# USB_to_UART.net
KiCad netlist of a schematic drawn in Altium Designer
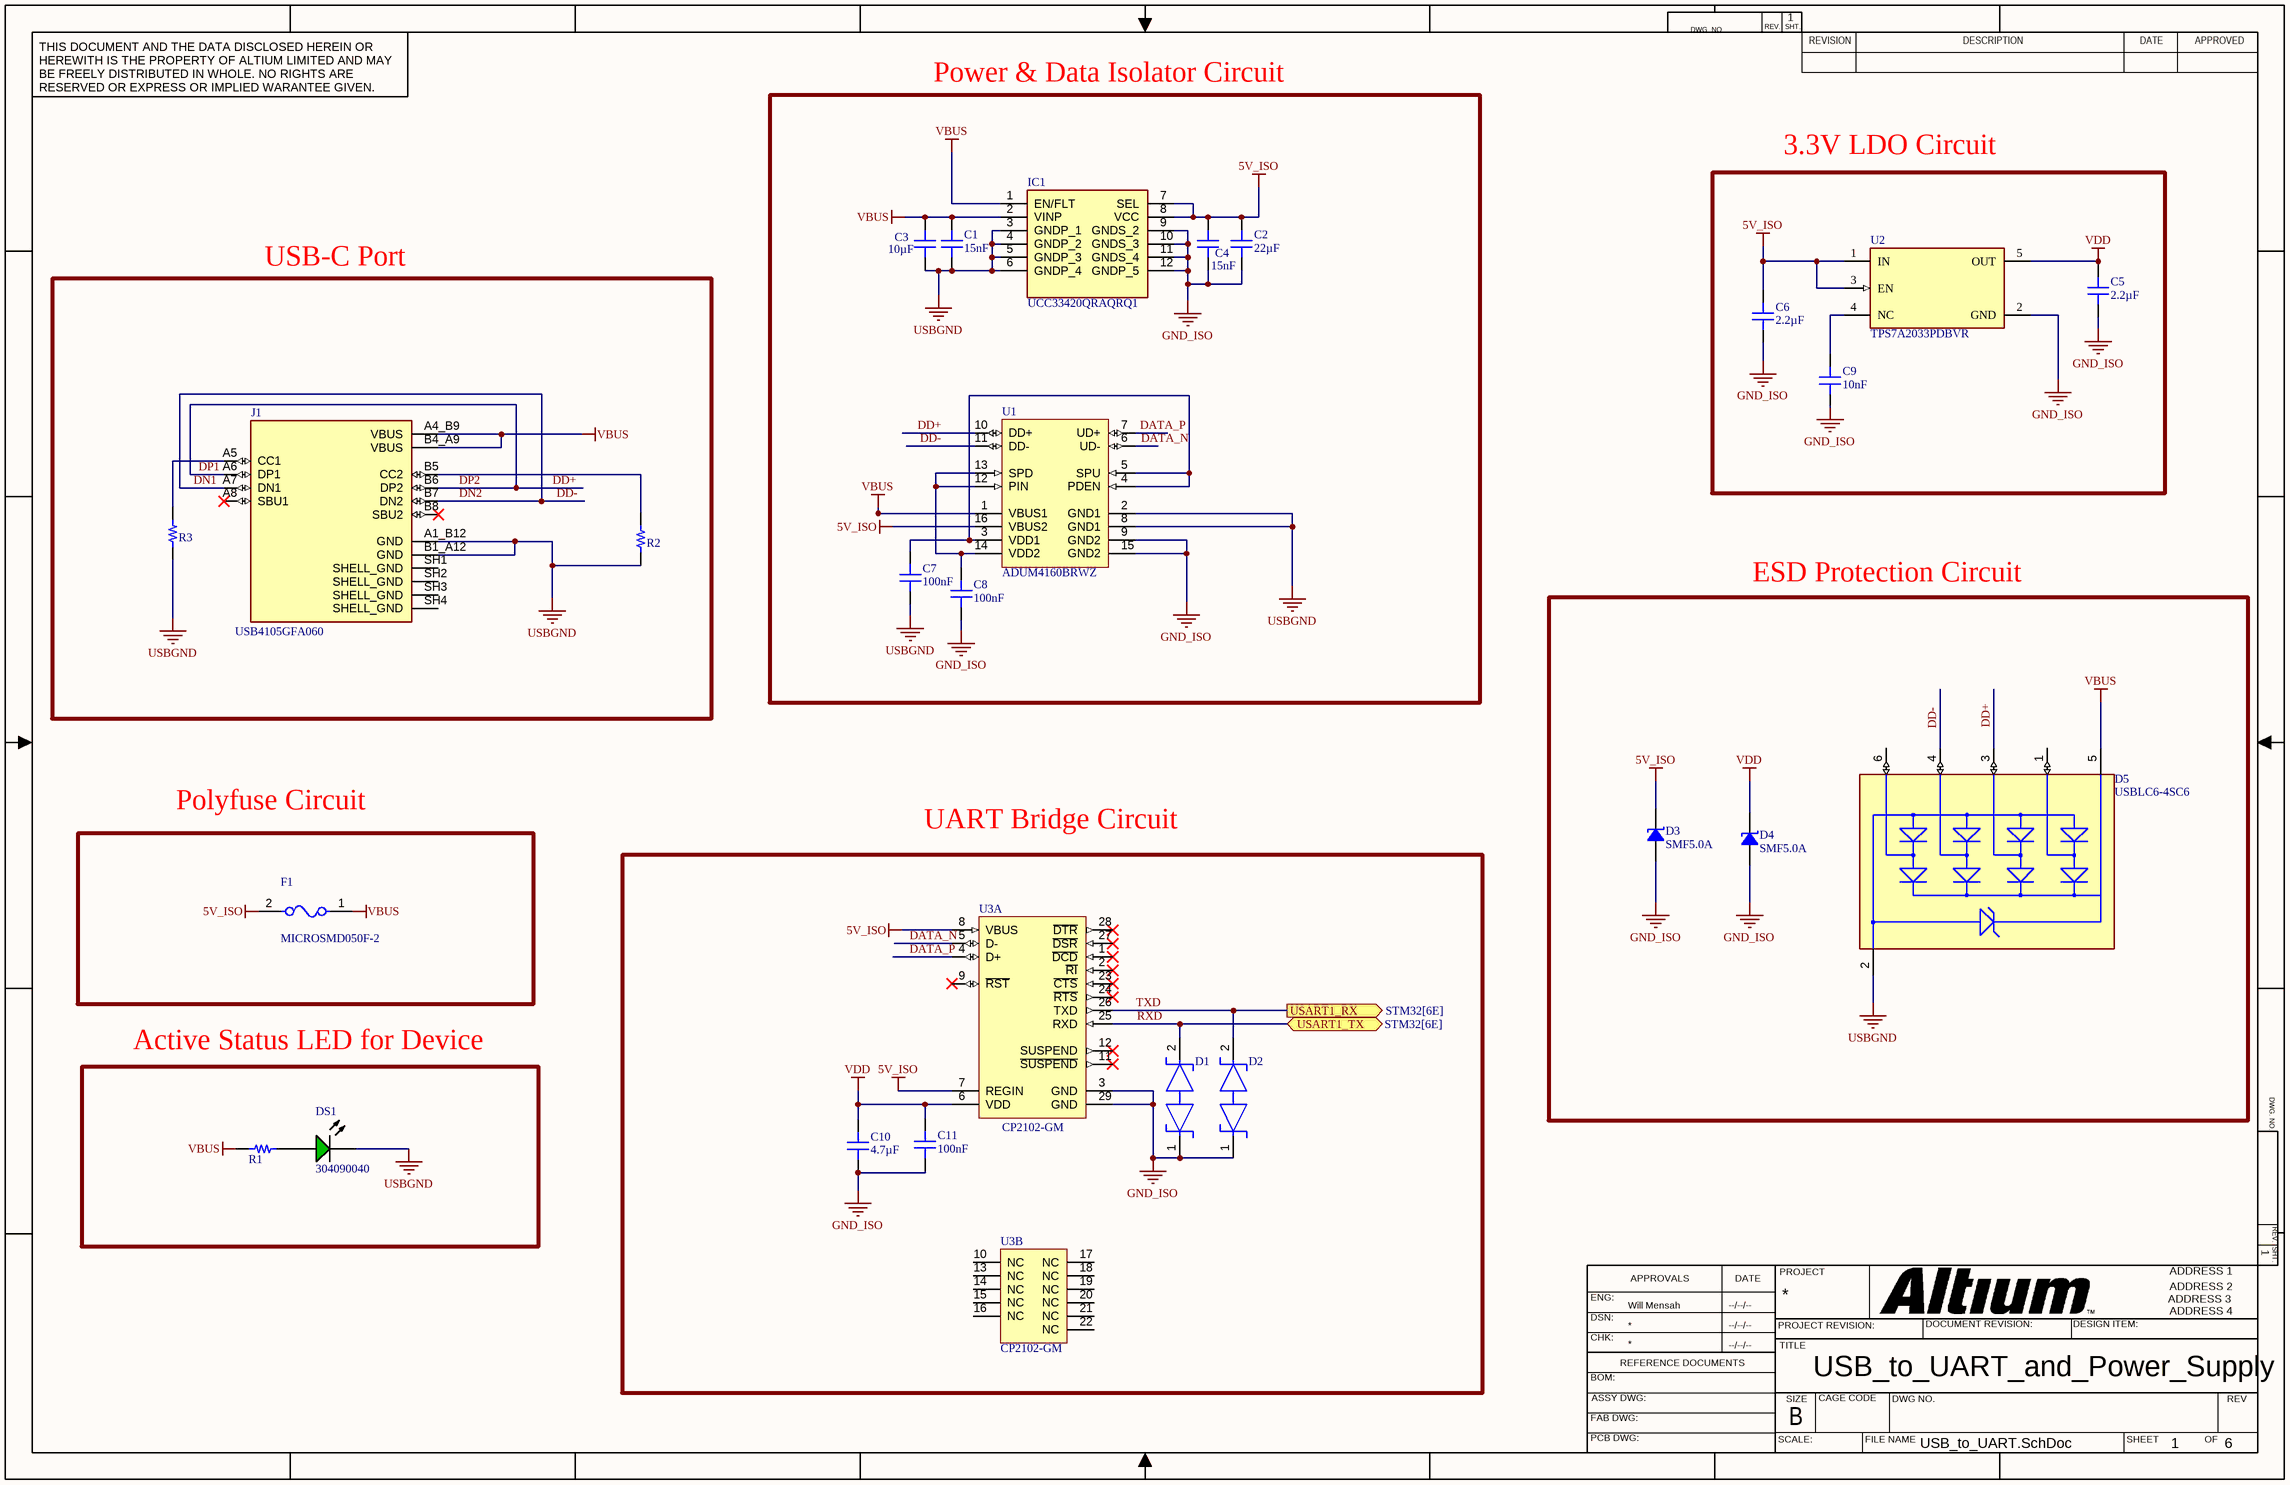
[diagram p0: USB_to_UART.SchDoc]

(export (version "E")
  (design (tool "Eeschema 10.0.6"))
  (components
    (comp (ref "C1")
      (value "15nF")
      (footprint "CAP 1206_3216 - 0.8MM")
      (description "CAP CER 15000PF 630V X7R 1206")
      (fields (field (name "PART NUMBER") "885342208013"))
      (libsource (lib "University of Massachusetts Lowell") (part "CAPACITOR"))
    )
    (comp (ref "C2")
      (value "22µF")
      (footprint "MURATA - GRM32E")
      (description "CAP CER 22UF 25V X7R 1210")
      (fields (field (name "PART NUMBER") "GRM32ER71E226ME15L"))
      (libsource (lib "University of Massachusetts Lowell") (part "CAPACITOR"))
    )
    (comp (ref "C3")
      (value "10µF")
      (footprint "MURATA - GRM32E")
      (description "CAP CER 10UF 50V X7R 1210")
      (fields (field (name "PART NUMBER") "GRM32ER71H106MA12L"))
      (libsource (lib "University of Massachusetts Lowell") (part "CAPACITOR"))
    )
    (comp (ref "C4")
      (value "15nF")
      (footprint "CAP 1206_3216 - 0.8MM")
      (description "CAP CER 15000PF 630V X7R 1206")
      (fields (field (name "PART NUMBER") "885342208013"))
      (libsource (lib "University of Massachusetts Lowell") (part "CAPACITOR"))
    )
    (comp (ref "C5")
      (value "2.2µF")
      (footprint "MURATA CAP GCM31M 1206_3216")
      (description "CAP CER 2.2UF 100V X8L 1206")
      (fields (field (name "PART NUMBER") "GCM31CL8EL225KE07L"))
      (libsource (lib "University of Massachusetts Lowell") (part "CAPACITOR"))
    )
    (comp (ref "C6")
      (value "2.2µF")
      (footprint "MURATA CAP GCM31M 1206_3216")
      (description "CAP CER 2.2UF 100V X8L 1206")
      (fields (field (name "PART NUMBER") "GCM31CL8EL225KE07L"))
      (libsource (lib "University of Massachusetts Lowell") (part "CAPACITOR"))
    )
    (comp (ref "C7")
      (value "100nF")
      (footprint "MURATA CAP GCM31M 1206_3216")
      (description "CAP CER 0.1UF 50V C0G/NP0 1206")
      (fields (field (name "PART NUMBER") "GCM31C5C1H104FA16L"))
      (libsource (lib "University of Massachusetts Lowell") (part "CAPACITOR"))
    )
    (comp (ref "C8")
      (value "100nF")
      (footprint "MURATA CAP GCM31M 1206_3216")
      (description "CAP CER 0.1UF 50V C0G/NP0 1206")
      (fields (field (name "PART NUMBER") "GCM31C5C1H104FA16L"))
      (libsource (lib "University of Massachusetts Lowell") (part "CAPACITOR"))
    )
    (comp (ref "C9")
      (value "10nF")
      (footprint "MURATA CAP GRM31B 1206_3216")
      (description "CAP CER 10000PF 250V U2J 1206")
      (fields (field (name "PART NUMBER") "GRM31B7U2E103JW31L"))
      (libsource (lib "University of Massachusetts Lowell") (part "CAPACITOR"))
    )
    (comp (ref "C10")
      (value "4.7µF")
      (footprint "MURATA GRM21B 0805_2012")
      (description "CAP CER 4.7UF 10V X7R 0805")
      (fields (field (name "PART NUMBER") "GRM21BR71A475KE51L"))
      (libsource (lib "University of Massachusetts Lowell") (part "CAPACITOR"))
    )
    (comp (ref "C11")
      (value "100nF")
      (footprint "MURATA CAP GCM31M 1206_3216")
      (description "CAP CER 0.1UF 50V C0G/NP0 1206")
      (fields (field (name "PART NUMBER") "GCM31C5C1H104FA16L"))
      (libsource (lib "University of Massachusetts Lowell") (part "CAPACITOR"))
    )
    (comp (ref "D1")
      (value "TPD1E10B06DPYR")
      (footprint "FP-DPY0002A-MFG")
      (description "TVS DIODE 5.5V 14V 2X1SON")
      (fields (field (name "MANUFACTURER") "Texas Instruments"))
      (libsource (lib "Altium Content Vault") (part "208e19b57522434895fa003e5d5b197"))
    )
    (comp (ref "D2")
      (value "TPD1E10B06DPYR")
      (footprint "FP-DPY0002A-MFG")
      (description "TVS DIODE 5.5V 14V 2X1SON")
      (fields (field (name "MANUFACTURER") "Texas Instruments"))
      (libsource (lib "Altium Content Vault") (part "208e19b57522434895fa003e5d5b197"))
    )
    (comp (ref "D3")
      (value "SMF5.0A")
      (footprint "SOD123F")
      (description "TVS SOD123FL 5V 200W UNIDIR")
      (libsource (lib "University of Massachusetts Lowell") (part "DIODE TVS UNI"))
    )
    (comp (ref "D4")
      (value "SMF5.0A")
      (footprint "SOD123F")
      (description "TVS SOD123FL 5V 200W UNIDIR")
      (libsource (lib "University of Massachusetts Lowell") (part "DIODE TVS UNI"))
    )
    (comp (ref "D5")
      (value "USBLC6-4SC6")
      (footprint "FP-SOT23-6L-MFG")
      (description "TVS DIODE 5.25V 17V SOT23-6")
      (fields
        (field (name "MANUFACTURER") "STMicroelectronics")
        (field (name "OCTOPART") "https://octopart.com/usblc6-4sc6-stmicroelectronics-347147")
      )
      (libsource (lib "Altium Content Vault") (part "3e70b616ccdc4c88b528e1820c4a7da"))
    )
    (comp (ref "DS1")
      (value "304090040")
      (footprint "LED-2P-2.28-3MM")
      (description "Green LED, 80 mW, 20 mA, -25 to 85 degC, 2-Pin THD")
      (fields (field (name "MANUFACTURER") "Shenzhen CGX"))
      (libsource (lib "University of Massachusetts Lowell") (part "LED-GREEN-AK-2"))
    )
    (comp (ref "F1")
      (value "MICROSMD050F-2")
      (footprint "FP-microSMD-MFG")
      (description "PTC RESET FUSE 13.2V 500MA 1210")
      (fields
        (field (name "MANUFACTURER") "Littelfuse")
        (field (name "OCTOPART") "https://octopart.com/microsmd050f-2-littelfuse-74214982")
      )
      (libsource (lib "Altium Content Vault") (part "5bcf9b9f640e542cf0359d10258e979"))
    )
    (comp (ref "IC1")
      (value "UCC33420QRAQRQ1")
      (footprint "SamacSys:UCC33020QRAQRQ1")
      (description "Integrated Circuit")
      (fields (field (name "MOUSER PART NUMBER") "595-UCC33420QRAQRQ1"))
      (libsource (lib "*") (part "UCC33420QRAQRQ1"))
    )
    (comp (ref "J1")
      (value "USB4105GFA060")
      (footprint "GCT_USB4105GFA060")
      (fields (field (name "MF") "Global Connector Technology"))
      (libsource (lib "University of Massachusetts Lowell") (part "USB4105GFA060"))
    )
    (comp (ref "R1")
      (value "RC1206FR-101KL")
      (footprint "YAGEO RES 1206_3216")
      (description "RES 1K OHM 1% 1/4W 1206")
      (libsource (lib "University of Massachusetts Lowell") (part "RESISTOR"))
    )
    (comp (ref "R2")
      (value "RP1206BRD075K1L")
      (footprint "YAGEO RES 1206_3216")
      (description "RES 5.1K OHM 0.1% 1/4W 1206")
      (libsource (lib "University of Massachusetts Lowell") (part "RESISTOR"))
    )
    (comp (ref "R3")
      (value "RP1206BRD075K1L")
      (footprint "YAGEO RES 1206_3216")
      (description "RES 5.1K OHM 0.1% 1/4W 1206")
      (libsource (lib "University of Massachusetts Lowell") (part "RESISTOR"))
    )
    (comp (ref "U1")
      (value "ADUM4160BRWZ")
      (footprint "RW-16_L")
      (fields (field (name "MANUFACTURER") "Analog Devices"))
      (libsource (lib "Altium Content Vault") (part "ADI-ADUM4160-16"))
    )
    (comp (ref "U2")
      (value "TPS7A2033PDBVR")
      (footprint "FP-DBV0005A-MFG")
      (description "IC REG LINEAR 3.3V 300MA SOT23-5")
      (libsource (lib "Altium Content Vault") (part "76aa7ad0ceb1012e0d85aeafc53095f"))
    )
    (comp (ref "U3")
      (value "CP2102-GM")
      (footprint "SLAB-QFN-28-3125x3125TP_N")
      (description "Single-Chip USB to UART Bridge, 1024 Bytes EEPROM, -40 to 85 degC, 28-pin QFN, Tube")
      (fields (field (name "MANUFACTURER") "Silicon Labs"))
      (libsource (lib "Altium Content Vault") (part "SLAB-CP210X-QFN-28-29"))
    )
  )
  (nets
    (net (code "1") (name "/DATA_N") (class "Default")
      (node (ref "U1") (pin "6") (pinfunction "UD-_6") (pintype "bidirectional"))
      (node (ref "U3") (pin "5") (pinfunction "D-_5") (pintype "bidirectional"))
    )
    (net (code "2") (name "/DATA_P") (class "Default")
      (node (ref "U1") (pin "7") (pinfunction "UD+_7") (pintype "bidirectional"))
      (node (ref "U3") (pin "4") (pinfunction "D+_4") (pintype "bidirectional"))
    )
    (net (code "3") (name "/DD+") (class "Default")
      (node (ref "D5") (pin "3") (pinfunction "I/O2_3") (pintype "bidirectional"))
      (node (ref "J1") (pin "A6") (pinfunction "DP1_A6") (pintype "bidirectional"))
      (node (ref "J1") (pin "B6") (pinfunction "DP2_B6") (pintype "bidirectional"))
      (node (ref "U1") (pin "10") (pinfunction "DD+_10") (pintype "bidirectional"))
    )
    (net (code "4") (name "/DD-") (class "Default")
      (node (ref "D5") (pin "4") (pinfunction "I/O3_4") (pintype "bidirectional"))
      (node (ref "J1") (pin "A7") (pinfunction "DN1_A7") (pintype "bidirectional"))
      (node (ref "J1") (pin "B7") (pinfunction "DN2_B7") (pintype "bidirectional"))
      (node (ref "U1") (pin "11") (pinfunction "DD-_11") (pintype "bidirectional"))
    )
    (net (code "5") (name "/RXD") (class "Default")
      (node (ref "D1") (pin "2") (pinfunction "2_2") (pintype "passive"))
      (node (ref "U3") (pin "25") (pinfunction "RXD_25") (pintype "input"))
    )
    (net (code "6") (name "/TXD") (class "Default")
      (node (ref "D2") (pin "2") (pinfunction "2_2") (pintype "passive"))
      (node (ref "U3") (pin "26") (pinfunction "TXD_26") (pintype "output"))
    )
    (net (code "7") (name "5V_ISO") (class "Default")
      (node (ref "C2") (pin "2") (pinfunction "2_2") (pintype "passive"))
      (node (ref "C4") (pin "2") (pinfunction "2_2") (pintype "passive"))
      (node (ref "C6") (pin "2") (pinfunction "2_2") (pintype "passive"))
      (node (ref "D3") (pin "2") (pinfunction "2_2") (pintype "passive"))
      (node (ref "F1") (pin "2") (pinfunction "2_2") (pintype "passive"))
      (node (ref "IC1") (pin "7") (pinfunction "SEL_7") (pintype "passive"))
      (node (ref "IC1") (pin "8") (pinfunction "VCC_8") (pintype "passive"))
      (node (ref "U1") (pin "16") (pinfunction "VBUS2_16") (pintype "power_in"))
      (node (ref "U2") (pin "1") (pinfunction "IN_1") (pintype "power_in"))
      (node (ref "U2") (pin "3") (pinfunction "EN_3") (pintype "input"))
      (node (ref "U3") (pin "7") (pinfunction "REGIN_7") (pintype "power_in"))
      (node (ref "U3") (pin "8") (pinfunction "VBUS_8") (pintype "input"))
    )
    (net (code "8") (name "GND_ISO") (class "Default")
      (node (ref "C10") (pin "1") (pinfunction "1_1") (pintype "passive"))
      (node (ref "C11") (pin "1") (pinfunction "1_1") (pintype "passive"))
      (node (ref "C2") (pin "1") (pinfunction "1_1") (pintype "passive"))
      (node (ref "C4") (pin "1") (pinfunction "1_1") (pintype "passive"))
      (node (ref "C5") (pin "1") (pinfunction "1_1") (pintype "passive"))
      (node (ref "C6") (pin "1") (pinfunction "1_1") (pintype "passive"))
      (node (ref "C8") (pin "1") (pinfunction "1_1") (pintype "passive"))
      (node (ref "C9") (pin "1") (pinfunction "1_1") (pintype "passive"))
      (node (ref "D1") (pin "1") (pinfunction "1_1") (pintype "passive"))
      (node (ref "D2") (pin "1") (pinfunction "1_1") (pintype "passive"))
      (node (ref "D3") (pin "1") (pinfunction "1_1") (pintype "passive"))
      (node (ref "D4") (pin "1") (pinfunction "1_1") (pintype "passive"))
      (node (ref "IC1") (pin "10") (pinfunction "GNDS_3_10") (pintype "passive"))
      (node (ref "IC1") (pin "11") (pinfunction "GNDS_4_11") (pintype "passive"))
      (node (ref "IC1") (pin "12") (pinfunction "GNDP_5_12") (pintype "passive"))
      (node (ref "IC1") (pin "9") (pinfunction "GNDS_2_9") (pintype "passive"))
      (node (ref "U1") (pin "15") (pinfunction "GND2_15") (pintype "power_in"))
      (node (ref "U1") (pin "9") (pinfunction "GND2_9") (pintype "power_in"))
      (node (ref "U2") (pin "2") (pinfunction "GND_2") (pintype "power_in"))
      (node (ref "U3") (pin "29") (pinfunction "GND_29") (pintype "power_in"))
      (node (ref "U3") (pin "3") (pinfunction "GND_3") (pintype "power_in"))
    )
    (net (code "9") (name "Net-(DS1-A)") (class "Default")
      (node (ref "DS1") (pin "1") (pinfunction "A_1") (pintype "passive"))
      (node (ref "R1") (pin "1") (pinfunction "1_1") (pintype "passive"))
    )
    (net (code "10") (name "Net-(J1-CC1)") (class "Default")
      (node (ref "J1") (pin "A5") (pinfunction "CC1_A5") (pintype "bidirectional"))
      (node (ref "R3") (pin "1") (pinfunction "1_1") (pintype "passive"))
    )
    (net (code "11") (name "Net-(J1-CC2)") (class "Default")
      (node (ref "J1") (pin "B5") (pinfunction "CC2_B5") (pintype "bidirectional"))
      (node (ref "R2") (pin "2") (pinfunction "2_2") (pintype "passive"))
    )
    (net (code "12") (name "Net-(U1-PDEN)") (class "Default")
      (node (ref "C7") (pin "2") (pinfunction "2_2") (pintype "passive"))
      (node (ref "U1") (pin "3") (pinfunction "VDD1_3") (pintype "power_in"))
      (node (ref "U1") (pin "4") (pinfunction "PDEN_4") (pintype "input"))
      (node (ref "U1") (pin "5") (pinfunction "SPU_5") (pintype "input"))
    )
    (net (code "13") (name "Net-(U1-PIN)") (class "Default")
      (node (ref "C8") (pin "2") (pinfunction "2_2") (pintype "passive"))
      (node (ref "U1") (pin "12") (pinfunction "PIN_12") (pintype "input"))
      (node (ref "U1") (pin "13") (pinfunction "SPD_13") (pintype "input"))
      (node (ref "U1") (pin "14") (pinfunction "VDD2_14") (pintype "power_in"))
    )
    (net (code "14") (name "Net-(U2-NC)") (class "Default")
      (node (ref "C9") (pin "2") (pinfunction "2_2") (pintype "passive"))
      (node (ref "U2") (pin "4") (pinfunction "NC_4") (pintype "passive"))
    )
    (net (code "15") (name "USBGND") (class "Default")
      (node (ref "C1") (pin "1") (pinfunction "1_1") (pintype "passive"))
      (node (ref "C3") (pin "1") (pinfunction "1_1") (pintype "passive"))
      (node (ref "C7") (pin "1") (pinfunction "1_1") (pintype "passive"))
      (node (ref "D5") (pin "2") (pinfunction "GND_2") (pintype "power_in"))
      (node (ref "DS1") (pin "2") (pinfunction "K_2") (pintype "passive"))
      (node (ref "IC1") (pin "3") (pinfunction "GNDP_1_3") (pintype "passive"))
      (node (ref "IC1") (pin "4") (pinfunction "GNDP_2_4") (pintype "passive"))
      (node (ref "IC1") (pin "5") (pinfunction "GNDP_3_5") (pintype "passive"))
      (node (ref "IC1") (pin "6") (pinfunction "GNDP_4_6") (pintype "passive"))
      (node (ref "J1") (pin "A1_B12") (pinfunction "GND_A1_B12") (pintype "power_in"))
      (node (ref "J1") (pin "B1_A12") (pinfunction "GND_B1_A12") (pintype "power_in"))
      (node (ref "R2") (pin "1") (pinfunction "1_1") (pintype "passive"))
      (node (ref "R3") (pin "2") (pinfunction "2_2") (pintype "passive"))
      (node (ref "U1") (pin "2") (pinfunction "GND1_2") (pintype "power_in"))
      (node (ref "U1") (pin "8") (pinfunction "GND1_8") (pintype "power_in"))
    )
    (net (code "16") (name "VBUS") (class "Default")
      (node (ref "C1") (pin "2") (pinfunction "2_2") (pintype "passive"))
      (node (ref "C3") (pin "2") (pinfunction "2_2") (pintype "passive"))
      (node (ref "D5") (pin "5") (pinfunction "VBUS_5") (pintype "power_in"))
      (node (ref "F1") (pin "1") (pinfunction "1_1") (pintype "passive"))
      (node (ref "IC1") (pin "1") (pinfunction "EN/FLT_1") (pintype "passive"))
      (node (ref "IC1") (pin "2") (pinfunction "VINP_2") (pintype "passive"))
      (node (ref "J1") (pin "A4_B9") (pinfunction "VBUS_A4_B9") (pintype "power_in"))
      (node (ref "J1") (pin "B4_A9") (pinfunction "VBUS_B4_A9") (pintype "power_in"))
      (node (ref "R1") (pin "2") (pinfunction "2_2") (pintype "passive"))
      (node (ref "U1") (pin "1") (pinfunction "VBUS1_1") (pintype "power_in"))
    )
    (net (code "17") (name "VDD") (class "Default")
      (node (ref "C10") (pin "2") (pinfunction "2_2") (pintype "passive"))
      (node (ref "C11") (pin "2") (pinfunction "2_2") (pintype "passive"))
      (node (ref "C5") (pin "2") (pinfunction "2_2") (pintype "passive"))
      (node (ref "D4") (pin "2") (pinfunction "2_2") (pintype "passive"))
      (node (ref "U2") (pin "5") (pinfunction "OUT_5") (pintype "passive"))
      (node (ref "U3") (pin "6") (pinfunction "VDD_6") (pintype "power_in"))
    )
    (net (code "18") (name "unconnected-(D5-I{slash}O1-Pad1)") (class "Default")
      (node (ref "D5") (pin "1") (pinfunction "I/O1_1") (pintype "bidirectional"))
    )
    (net (code "19") (name "unconnected-(D5-I{slash}O4-Pad6)") (class "Default")
      (node (ref "D5") (pin "6") (pinfunction "I/O4_6") (pintype "bidirectional"))
    )
    (net (code "20") (name "unconnected-(J1-SBU1-PadA8)") (class "Default")
      (node (ref "J1") (pin "A8") (pinfunction "SBU1_A8") (pintype "bidirectional+no_connect"))
    )
    (net (code "21") (name "unconnected-(J1-SBU2-PadB8)") (class "Default")
      (node (ref "J1") (pin "B8") (pinfunction "SBU2_B8") (pintype "bidirectional+no_connect"))
    )
    (net (code "22") (name "unconnected-(J1-SHELL_GND-PadSH1)") (class "Default")
      (node (ref "J1") (pin "SH1") (pinfunction "SHELL_GND_SH1") (pintype "power_in"))
    )
    (net (code "23") (name "unconnected-(J1-SHELL_GND-PadSH2)") (class "Default")
      (node (ref "J1") (pin "SH2") (pinfunction "SHELL_GND_SH2") (pintype "power_in"))
    )
    (net (code "24") (name "unconnected-(J1-SHELL_GND-PadSH3)") (class "Default")
      (node (ref "J1") (pin "SH3") (pinfunction "SHELL_GND_SH3") (pintype "power_in"))
    )
    (net (code "25") (name "unconnected-(J1-SHELL_GND-PadSH4)") (class "Default")
      (node (ref "J1") (pin "SH4") (pinfunction "SHELL_GND_SH4") (pintype "power_in"))
    )
    (net (code "26") (name "unconnected-(U3A-SUSPEND-Pad12)") (class "Default")
      (node (ref "U3") (pin "12") (pinfunction "SUSPEND_12") (pintype "output+no_connect"))
    )
    (net (code "27") (name "unconnected-(U3A-~{CTS}-Pad23)") (class "Default")
      (node (ref "U3") (pin "23") (pinfunction "~{CTS}_23") (pintype "input+no_connect"))
    )
    (net (code "28") (name "unconnected-(U3A-~{DCD}-Pad1)") (class "Default")
      (node (ref "U3") (pin "1") (pinfunction "~{DCD}_1") (pintype "input+no_connect"))
    )
    (net (code "29") (name "unconnected-(U3A-~{DSR}-Pad27)") (class "Default")
      (node (ref "U3") (pin "27") (pinfunction "~{DSR}_27") (pintype "input+no_connect"))
    )
    (net (code "30") (name "unconnected-(U3A-~{DTR}-Pad28)") (class "Default")
      (node (ref "U3") (pin "28") (pinfunction "~{DTR}_28") (pintype "output+no_connect"))
    )
    (net (code "31") (name "unconnected-(U3A-~{RI}-Pad2)") (class "Default")
      (node (ref "U3") (pin "2") (pinfunction "~{RI}_2") (pintype "input+no_connect"))
    )
    (net (code "32") (name "unconnected-(U3A-~{RST}-Pad9)") (class "Default")
      (node (ref "U3") (pin "9") (pinfunction "~{RST}_9") (pintype "bidirectional+no_connect"))
    )
    (net (code "33") (name "unconnected-(U3A-~{RTS}-Pad24)") (class "Default")
      (node (ref "U3") (pin "24") (pinfunction "~{RTS}_24") (pintype "output+no_connect"))
    )
    (net (code "34") (name "unconnected-(U3A-~{SUSPEND}-Pad11)") (class "Default")
      (node (ref "U3") (pin "11") (pinfunction "~{SUSPEND}_11") (pintype "output+no_connect"))
    )
    (net (code "35") (name "unconnected-(U3B-NC-Pad10)") (class "Default")
      (node (ref "U3") (pin "10") (pinfunction "NC_10") (pintype "passive"))
    )
    (net (code "36") (name "unconnected-(U3B-NC-Pad13)") (class "Default")
      (node (ref "U3") (pin "13") (pinfunction "NC_13") (pintype "passive"))
    )
    (net (code "37") (name "unconnected-(U3B-NC-Pad14)") (class "Default")
      (node (ref "U3") (pin "14") (pinfunction "NC_14") (pintype "passive"))
    )
    (net (code "38") (name "unconnected-(U3B-NC-Pad15)") (class "Default")
      (node (ref "U3") (pin "15") (pinfunction "NC_15") (pintype "passive"))
    )
    (net (code "39") (name "unconnected-(U3B-NC-Pad16)") (class "Default")
      (node (ref "U3") (pin "16") (pinfunction "NC_16") (pintype "passive"))
    )
    (net (code "40") (name "unconnected-(U3B-NC-Pad17)") (class "Default")
      (node (ref "U3") (pin "17") (pinfunction "NC_17") (pintype "passive"))
    )
    (net (code "41") (name "unconnected-(U3B-NC-Pad18)") (class "Default")
      (node (ref "U3") (pin "18") (pinfunction "NC_18") (pintype "passive"))
    )
    (net (code "42") (name "unconnected-(U3B-NC-Pad19)") (class "Default")
      (node (ref "U3") (pin "19") (pinfunction "NC_19") (pintype "passive"))
    )
    (net (code "43") (name "unconnected-(U3B-NC-Pad20)") (class "Default")
      (node (ref "U3") (pin "20") (pinfunction "NC_20") (pintype "passive"))
    )
    (net (code "44") (name "unconnected-(U3B-NC-Pad21)") (class "Default")
      (node (ref "U3") (pin "21") (pinfunction "NC_21") (pintype "passive"))
    )
    (net (code "45") (name "unconnected-(U3B-NC-Pad22)") (class "Default")
      (node (ref "U3") (pin "22") (pinfunction "NC_22") (pintype "passive"))
    )
  )
)
